# tweeq-STAMP_I2C_EEPROM_v1.net
KiCad netlist of a schematic drawn in EAGLE
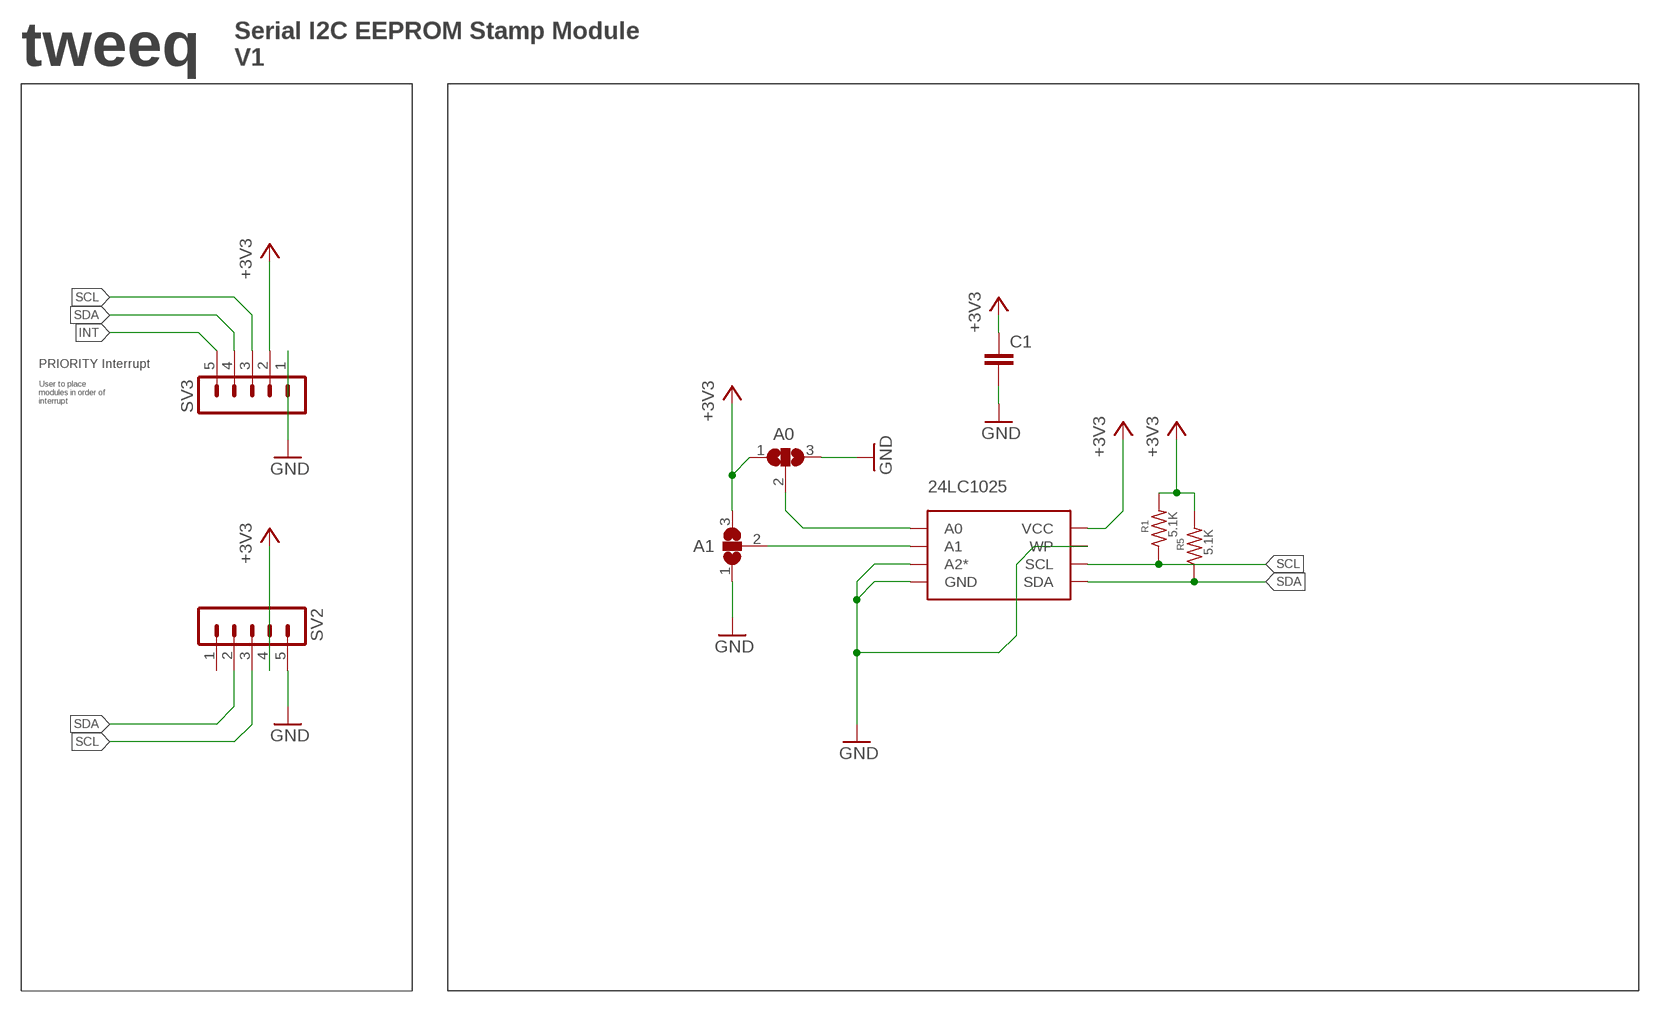
[diagram p0: schematic, sheet 1]

(export (version "E")
  (design (tool "Eeschema 10.0.6"))
  (components
    (comp (ref "24LC1025")
      (value "24LC1025")
      (footprint "eagle-import:SOIC8(W)")
      (libsource (lib "eagle-import") (part "24LC1025"))
    )
    (comp (ref "A0")
      (value "JUMPER_SJ2WS")
      (footprint "eagle-import:JUMPER_SJ_S")
      (libsource (lib "eagle-import") (part "JUMPER_SJ2WS"))
    )
    (comp (ref "A1")
      (value "JUMPER_SJ2WS")
      (footprint "eagle-import:JUMPER_SJ_S")
      (libsource (lib "eagle-import") (part "JUMPER_SJ2WS"))
    )
    (comp (ref "C1")
      (value "C-EUC0402K")
      (footprint "eagle-import:C0402K")
      (libsource (lib "eagle-import") (part "C-EUC0402K"))
    )
    (comp (ref "R1")
      (value "5.1K")
      (footprint "eagle-import:R0402")
      (libsource (lib "eagle-import") (part "R-US_R0402"))
    )
    (comp (ref "R5")
      (value "5.1K")
      (footprint "eagle-import:R0402")
      (libsource (lib "eagle-import") (part "R-US_R0402"))
    )
    (comp (ref "SV2")
      (value "M05-1STAMP")
      (footprint "eagle-import:1X05-1.5MM-STAMP")
      (libsource (lib "eagle-import") (part "M05-1STAMP"))
    )
    (comp (ref "SV3")
      (value "M05-1STAMP")
      (footprint "eagle-import:1X05-1.5MM-STAMP")
      (libsource (lib "eagle-import") (part "M05-1STAMP"))
    )
  )
  (nets
    (net (code "1") (name "+3V3") (class "Default")
      (node (ref "24LC1025") (pin "8") (pinfunction "VCC_8") (pintype "bidirectional"))
      (node (ref "A0") (pin "1") (pinfunction "1_1") (pintype "passive"))
      (node (ref "A1") (pin "3") (pinfunction "3_3") (pintype "passive"))
      (node (ref "C1") (pin "1") (pinfunction "1_1") (pintype "passive"))
      (node (ref "R1") (pin "2") (pinfunction "2_2") (pintype "passive"))
      (node (ref "R5") (pin "2") (pinfunction "2_2") (pintype "passive"))
      (node (ref "SV2") (pin "4") (pinfunction "4_4") (pintype "passive"))
      (node (ref "SV3") (pin "2") (pinfunction "2_2") (pintype "passive"))
    )
    (net (code "2") (name "GND") (class "Default")
      (node (ref "24LC1025") (pin "3") (pinfunction "A2*_3") (pintype "bidirectional"))
      (node (ref "24LC1025") (pin "4") (pinfunction "GND_4") (pintype "bidirectional"))
      (node (ref "24LC1025") (pin "7") (pinfunction "WP_7") (pintype "bidirectional"))
      (node (ref "A0") (pin "3") (pinfunction "3_3") (pintype "passive"))
      (node (ref "A1") (pin "1") (pinfunction "1_1") (pintype "passive"))
      (node (ref "C1") (pin "2") (pinfunction "2_2") (pintype "passive"))
      (node (ref "SV2") (pin "5") (pinfunction "5_5") (pintype "passive"))
      (node (ref "SV3") (pin "1") (pinfunction "1_1") (pintype "passive"))
    )
    (net (code "3") (name "INT") (class "Default")
      (node (ref "SV3") (pin "5") (pinfunction "5_5") (pintype "passive"))
    )
    (net (code "4") (name "Net-(24LC1025-A0)") (class "Default")
      (node (ref "24LC1025") (pin "1") (pinfunction "A0_1") (pintype "bidirectional"))
      (node (ref "A0") (pin "2") (pinfunction "2_2") (pintype "passive"))
    )
    (net (code "5") (name "Net-(24LC1025-A1)") (class "Default")
      (node (ref "24LC1025") (pin "2") (pinfunction "A1_2") (pintype "bidirectional"))
      (node (ref "A1") (pin "2") (pinfunction "2_2") (pintype "passive"))
    )
    (net (code "6") (name "SCL") (class "Default")
      (node (ref "24LC1025") (pin "6") (pinfunction "SCL_6") (pintype "bidirectional"))
      (node (ref "R1") (pin "1") (pinfunction "1_1") (pintype "passive"))
      (node (ref "SV2") (pin "3") (pinfunction "3_3") (pintype "passive"))
      (node (ref "SV3") (pin "3") (pinfunction "3_3") (pintype "passive"))
    )
    (net (code "7") (name "SDA") (class "Default")
      (node (ref "24LC1025") (pin "5") (pinfunction "SDA_5") (pintype "bidirectional"))
      (node (ref "R5") (pin "1") (pinfunction "1_1") (pintype "passive"))
      (node (ref "SV2") (pin "2") (pinfunction "2_2") (pintype "passive"))
      (node (ref "SV3") (pin "4") (pinfunction "4_4") (pintype "passive"))
    )
    (net (code "8") (name "unconnected-(SV2-Pad1)") (class "Default")
      (node (ref "SV2") (pin "1") (pinfunction "1_1") (pintype "passive"))
    )
  )
)
